# fredisp.net
KiCad netlist of a schematic drawn in EAGLE
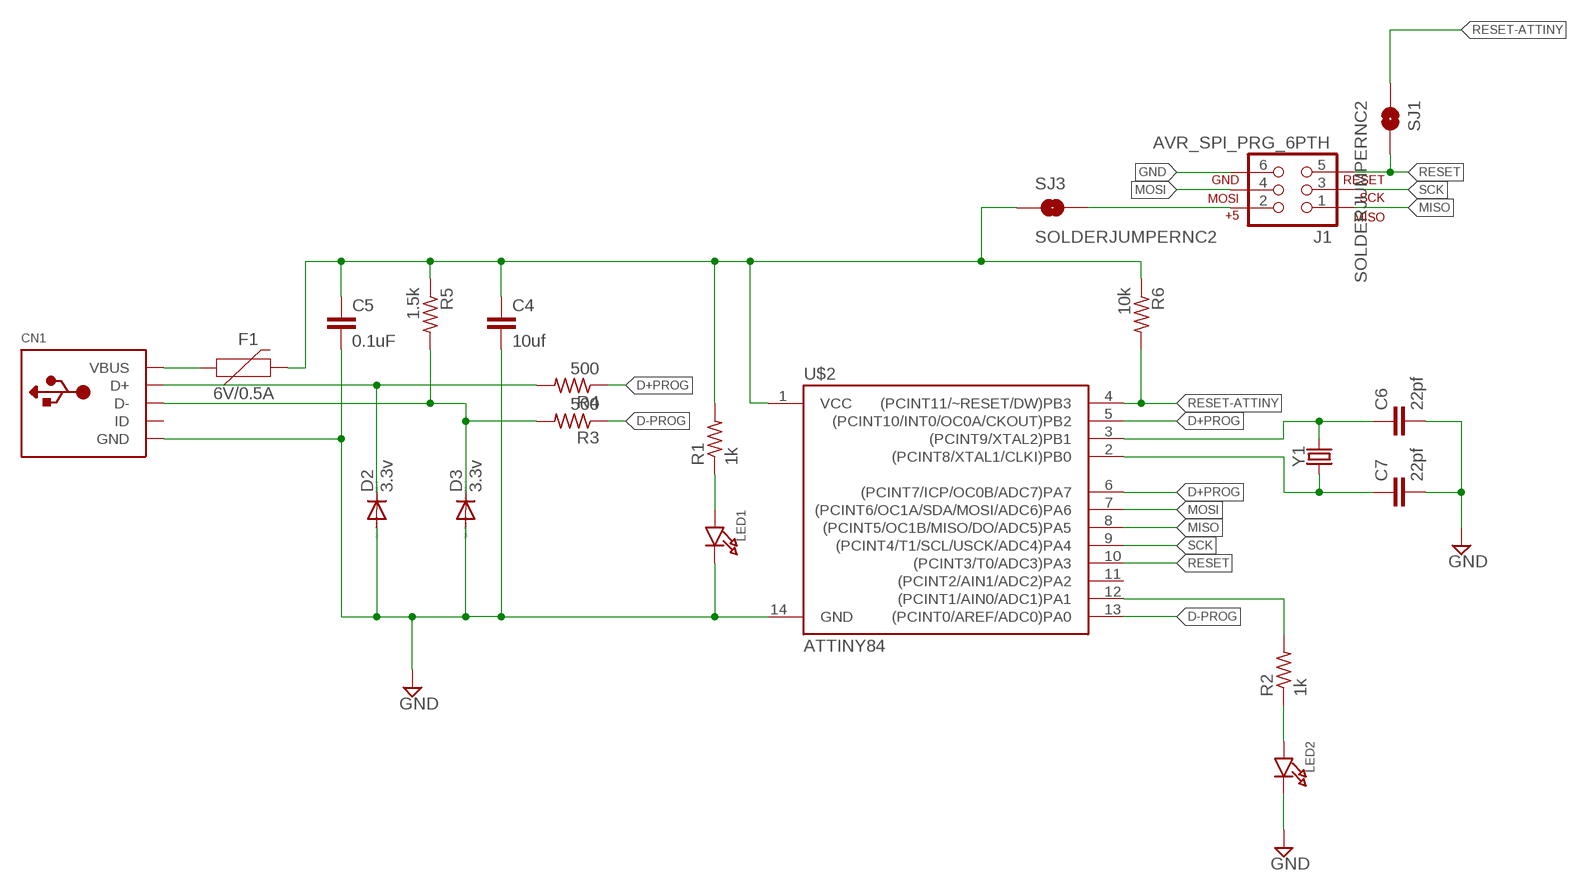
[diagram p0: schematic, sheet 1]

(export (version "E")
  (design (tool "Eeschema 10.0.6"))
  (components
    (comp (ref "C4")
      (value "10uf")
      (footprint "eagle-import:C1206")
      (libsource (lib "eagle-import") (part "C-EUC1206"))
    )
    (comp (ref "C5")
      (value "0.1uF")
      (footprint "eagle-import:C0805")
      (libsource (lib "eagle-import") (part "resistor_C-EUC0805"))
    )
    (comp (ref "C6")
      (value "22pf")
      (footprint "eagle-import:C0805")
      (libsource (lib "eagle-import") (part "resistor_C-EUC0805"))
    )
    (comp (ref "C7")
      (value "22pf")
      (footprint "eagle-import:C0805")
      (libsource (lib "eagle-import") (part "resistor_C-EUC0805"))
    )
    (comp (ref "CN1")
      (value "USBMINIB")
      (footprint "eagle-import:USB-MINIB")
      (libsource (lib "eagle-import") (part "USBMINIB"))
    )
    (comp (ref "D2")
      (value "3.3v")
      (footprint "eagle-import:SOD323-W")
      (libsource (lib "eagle-import") (part "DIODE-SOD323-W"))
    )
    (comp (ref "D3")
      (value "3.3v")
      (footprint "eagle-import:SOD323-W")
      (libsource (lib "eagle-import") (part "DIODE-SOD323-W"))
    )
    (comp (ref "F1")
      (value "6V/0.5A")
      (footprint "eagle-import:1206")
      (libsource (lib "eagle-import") (part "PPTC_HALF-AMP"))
    )
    (comp (ref "J1")
      (value "AVR_SPI_PRG_6PTH")
      (footprint "eagle-import:2X3")
      (libsource (lib "eagle-import") (part "AVR_SPI_PRG_6PTH"))
    )
    (comp (ref "LED1")
      (value "LED0805")
      (footprint "eagle-import:CHIPLED_0805")
      (libsource (lib "eagle-import") (part "LED0805"))
    )
    (comp (ref "LED2")
      (value "LED0805")
      (footprint "eagle-import:CHIPLED_0805")
      (libsource (lib "eagle-import") (part "LED0805"))
    )
    (comp (ref "R1")
      (value "1k")
      (footprint "eagle-import:R0805")
      (libsource (lib "eagle-import") (part "R-US_R0805"))
    )
    (comp (ref "R2")
      (value "1k")
      (footprint "eagle-import:R0805")
      (libsource (lib "eagle-import") (part "R-US_R0805"))
    )
    (comp (ref "R3")
      (value "500")
      (footprint "eagle-import:R0805")
      (libsource (lib "eagle-import") (part "R-US_R0805"))
    )
    (comp (ref "R4")
      (value "500")
      (footprint "eagle-import:R0805")
      (libsource (lib "eagle-import") (part "R-US_R0805"))
    )
    (comp (ref "R5")
      (value "1.5k")
      (footprint "eagle-import:R0805")
      (libsource (lib "eagle-import") (part "R-US_R0805"))
    )
    (comp (ref "R6")
      (value "10k")
      (footprint "eagle-import:R0805")
      (libsource (lib "eagle-import") (part "R-US_R0805"))
    )
    (comp (ref "SJ1")
      (value "SOLDERJUMPERNC2")
      (footprint "eagle-import:SJ_2S-NOTRACE")
      (libsource (lib "eagle-import") (part "SOLDERJUMPERNC2"))
    )
    (comp (ref "SJ3")
      (value "SOLDERJUMPERNC2")
      (footprint "eagle-import:SJ_2S-NOTRACE")
      (libsource (lib "eagle-import") (part "SOLDERJUMPERNC2"))
    )
    (comp (ref "U$2")
      (value "ATTINY84")
      (footprint "eagle-import:SO14")
      (libsource (lib "eagle-import") (part "ATTINY84"))
    )
    (comp (ref "Y1")
      (value "CRYSTALSMD-3.2X2.5")
      (footprint "eagle-import:CRYSTAL-SMD-3.2X2.5MM")
      (libsource (lib "eagle-import") (part "CRYSTALSMD-3.2X2.5"))
    )
  )
  (nets
    (net (code "1") (name "/VCC") (class "Default")
      (node (ref "C4") (pin "1") (pinfunction "1_1") (pintype "passive"))
      (node (ref "C5") (pin "1") (pinfunction "1_1") (pintype "passive"))
      (node (ref "F1") (pin "2") (pinfunction "2_2") (pintype "bidirectional"))
      (node (ref "R1") (pin "2") (pinfunction "2_2") (pintype "passive"))
      (node (ref "R5") (pin "1") (pinfunction "1_1") (pintype "passive"))
      (node (ref "R6") (pin "1") (pinfunction "1_1") (pintype "passive"))
      (node (ref "SJ3") (pin "1") (pinfunction "1_1") (pintype "passive"))
      (node (ref "U$2") (pin "1") (pinfunction "VCC_1") (pintype "bidirectional"))
    )
    (net (code "2") (name "D+PROG") (class "Default")
      (node (ref "R4") (pin "1") (pinfunction "1_1") (pintype "passive"))
      (node (ref "U$2") (pin "5") (pinfunction "(PCINT10/INT0/OC0A/CKOUT)PB2_5") (pintype "bidirectional"))
      (node (ref "U$2") (pin "6") (pinfunction "(PCINT7/ICP/OC0B/ADC7)PA7_6") (pintype "bidirectional"))
    )
    (net (code "3") (name "D-PROG") (class "Default")
      (node (ref "R3") (pin "1") (pinfunction "1_1") (pintype "passive"))
      (node (ref "U$2") (pin "13") (pinfunction "(PCINT0/AREF/ADC0)PA0_13") (pintype "bidirectional"))
    )
    (net (code "4") (name "GND") (class "Default")
      (node (ref "C4") (pin "2") (pinfunction "2_2") (pintype "passive"))
      (node (ref "C5") (pin "2") (pinfunction "2_2") (pintype "passive"))
      (node (ref "C6") (pin "2") (pinfunction "2_2") (pintype "passive"))
      (node (ref "C7") (pin "2") (pinfunction "2_2") (pintype "passive"))
      (node (ref "CN1") (pin "GND") (pinfunction "GND_GND") (pintype "power_in"))
      (node (ref "D2") (pin "A") (pinfunction "A_A") (pintype "passive"))
      (node (ref "D3") (pin "A") (pinfunction "A_A") (pintype "passive"))
      (node (ref "J1") (pin "6") (pinfunction "6_6") (pintype "passive"))
      (node (ref "LED1") (pin "C") (pinfunction "C_C") (pintype "passive"))
      (node (ref "LED2") (pin "C") (pinfunction "C_C") (pintype "passive"))
      (node (ref "U$2") (pin "14") (pinfunction "GND_14") (pintype "bidirectional"))
    )
    (net (code "5") (name "MISO") (class "Default")
      (node (ref "J1") (pin "1") (pinfunction "1_1") (pintype "passive"))
      (node (ref "U$2") (pin "8") (pinfunction "(PCINT5/OC1B/MISO/DO/ADC5)PA5_8") (pintype "bidirectional"))
    )
    (net (code "6") (name "MOSI") (class "Default")
      (node (ref "J1") (pin "4") (pinfunction "4_4") (pintype "passive"))
      (node (ref "U$2") (pin "7") (pinfunction "(PCINT6/OC1A/SDA/MOSI/ADC6)PA6_7") (pintype "bidirectional"))
    )
    (net (code "7") (name "Net-(CN1-PadD+)") (class "Default")
      (node (ref "CN1") (pin "D+") (pinfunction "D+_D+") (pintype "bidirectional"))
      (node (ref "D2") (pin "C") (pinfunction "C_C") (pintype "passive"))
      (node (ref "R4") (pin "2") (pinfunction "2_2") (pintype "passive"))
    )
    (net (code "8") (name "Net-(CN1-PadD-)") (class "Default")
      (node (ref "CN1") (pin "D-") (pinfunction "D-_D-") (pintype "bidirectional"))
      (node (ref "D3") (pin "C") (pinfunction "C_C") (pintype "passive"))
      (node (ref "R3") (pin "2") (pinfunction "2_2") (pintype "passive"))
      (node (ref "R5") (pin "2") (pinfunction "2_2") (pintype "passive"))
    )
    (net (code "9") (name "Net-(CN1-PadVBUS)") (class "Default")
      (node (ref "CN1") (pin "VBUS") (pinfunction "VBUS_VBUS") (pintype "power_in"))
      (node (ref "F1") (pin "1") (pinfunction "1_1") (pintype "bidirectional"))
    )
    (net (code "10") (name "Net-(J1-Pad2)") (class "Default")
      (node (ref "J1") (pin "2") (pinfunction "2_2") (pintype "passive"))
      (node (ref "SJ3") (pin "2") (pinfunction "2_2") (pintype "passive"))
    )
    (net (code "11") (name "Net-(LED1-PadA)") (class "Default")
      (node (ref "LED1") (pin "A") (pinfunction "A_A") (pintype "passive"))
      (node (ref "R1") (pin "1") (pinfunction "1_1") (pintype "passive"))
    )
    (net (code "12") (name "Net-(LED2-PadA)") (class "Default")
      (node (ref "LED2") (pin "A") (pinfunction "A_A") (pintype "passive"))
      (node (ref "R2") (pin "1") (pinfunction "1_1") (pintype "passive"))
    )
    (net (code "13") (name "Net-(U$2-(PCINT1{slash}AIN0{slash}ADC1)PA1)") (class "Default")
      (node (ref "R2") (pin "2") (pinfunction "2_2") (pintype "passive"))
      (node (ref "U$2") (pin "12") (pinfunction "(PCINT1/AIN0/ADC1)PA1_12") (pintype "bidirectional"))
    )
    (net (code "14") (name "Net-(U$2-(PCINT8{slash}XTAL1{slash}CLKI)PB0)") (class "Default")
      (node (ref "C7") (pin "1") (pinfunction "1_1") (pintype "passive"))
      (node (ref "U$2") (pin "2") (pinfunction "(PCINT8/XTAL1/CLKI)PB0_2") (pintype "bidirectional"))
      (node (ref "Y1") (pin "1") (pinfunction "1_1") (pintype "passive"))
    )
    (net (code "15") (name "Net-(U$2-(PCINT9{slash}XTAL2)PB1)") (class "Default")
      (node (ref "C6") (pin "1") (pinfunction "1_1") (pintype "passive"))
      (node (ref "U$2") (pin "3") (pinfunction "(PCINT9/XTAL2)PB1_3") (pintype "bidirectional"))
      (node (ref "Y1") (pin "3") (pinfunction "2_3") (pintype "passive"))
    )
    (net (code "16") (name "RESET") (class "Default")
      (node (ref "J1") (pin "5") (pinfunction "5_5") (pintype "passive"))
      (node (ref "SJ1") (pin "2") (pinfunction "2_2") (pintype "passive"))
      (node (ref "U$2") (pin "10") (pinfunction "(PCINT3/T0/ADC3)PA3_10") (pintype "bidirectional"))
    )
    (net (code "17") (name "RESET-ATTINY") (class "Default")
      (node (ref "R6") (pin "2") (pinfunction "2_2") (pintype "passive"))
      (node (ref "SJ1") (pin "1") (pinfunction "1_1") (pintype "passive"))
      (node (ref "U$2") (pin "4") (pinfunction "(PCINT11/~{RESET/DW})PB3_4") (pintype "bidirectional"))
    )
    (net (code "18") (name "SCK") (class "Default")
      (node (ref "J1") (pin "3") (pinfunction "3_3") (pintype "passive"))
      (node (ref "U$2") (pin "9") (pinfunction "(PCINT4/T1/SCL/USCK/ADC4)PA4_9") (pintype "bidirectional"))
    )
    (net (code "19") (name "unconnected-(CN1-PadID)") (class "Default")
      (node (ref "CN1") (pin "ID") (pinfunction "ID_ID") (pintype "bidirectional"))
    )
    (net (code "20") (name "unconnected-(U$2-(PCINT2{slash}AIN1{slash}ADC2)PA2-Pad11)") (class "Default")
      (node (ref "U$2") (pin "11") (pinfunction "(PCINT2/AIN1/ADC2)PA2_11") (pintype "bidirectional"))
    )
  )
)
